# LEDs_in_top.net
KiCad netlist of a schematic drawn in EAGLE
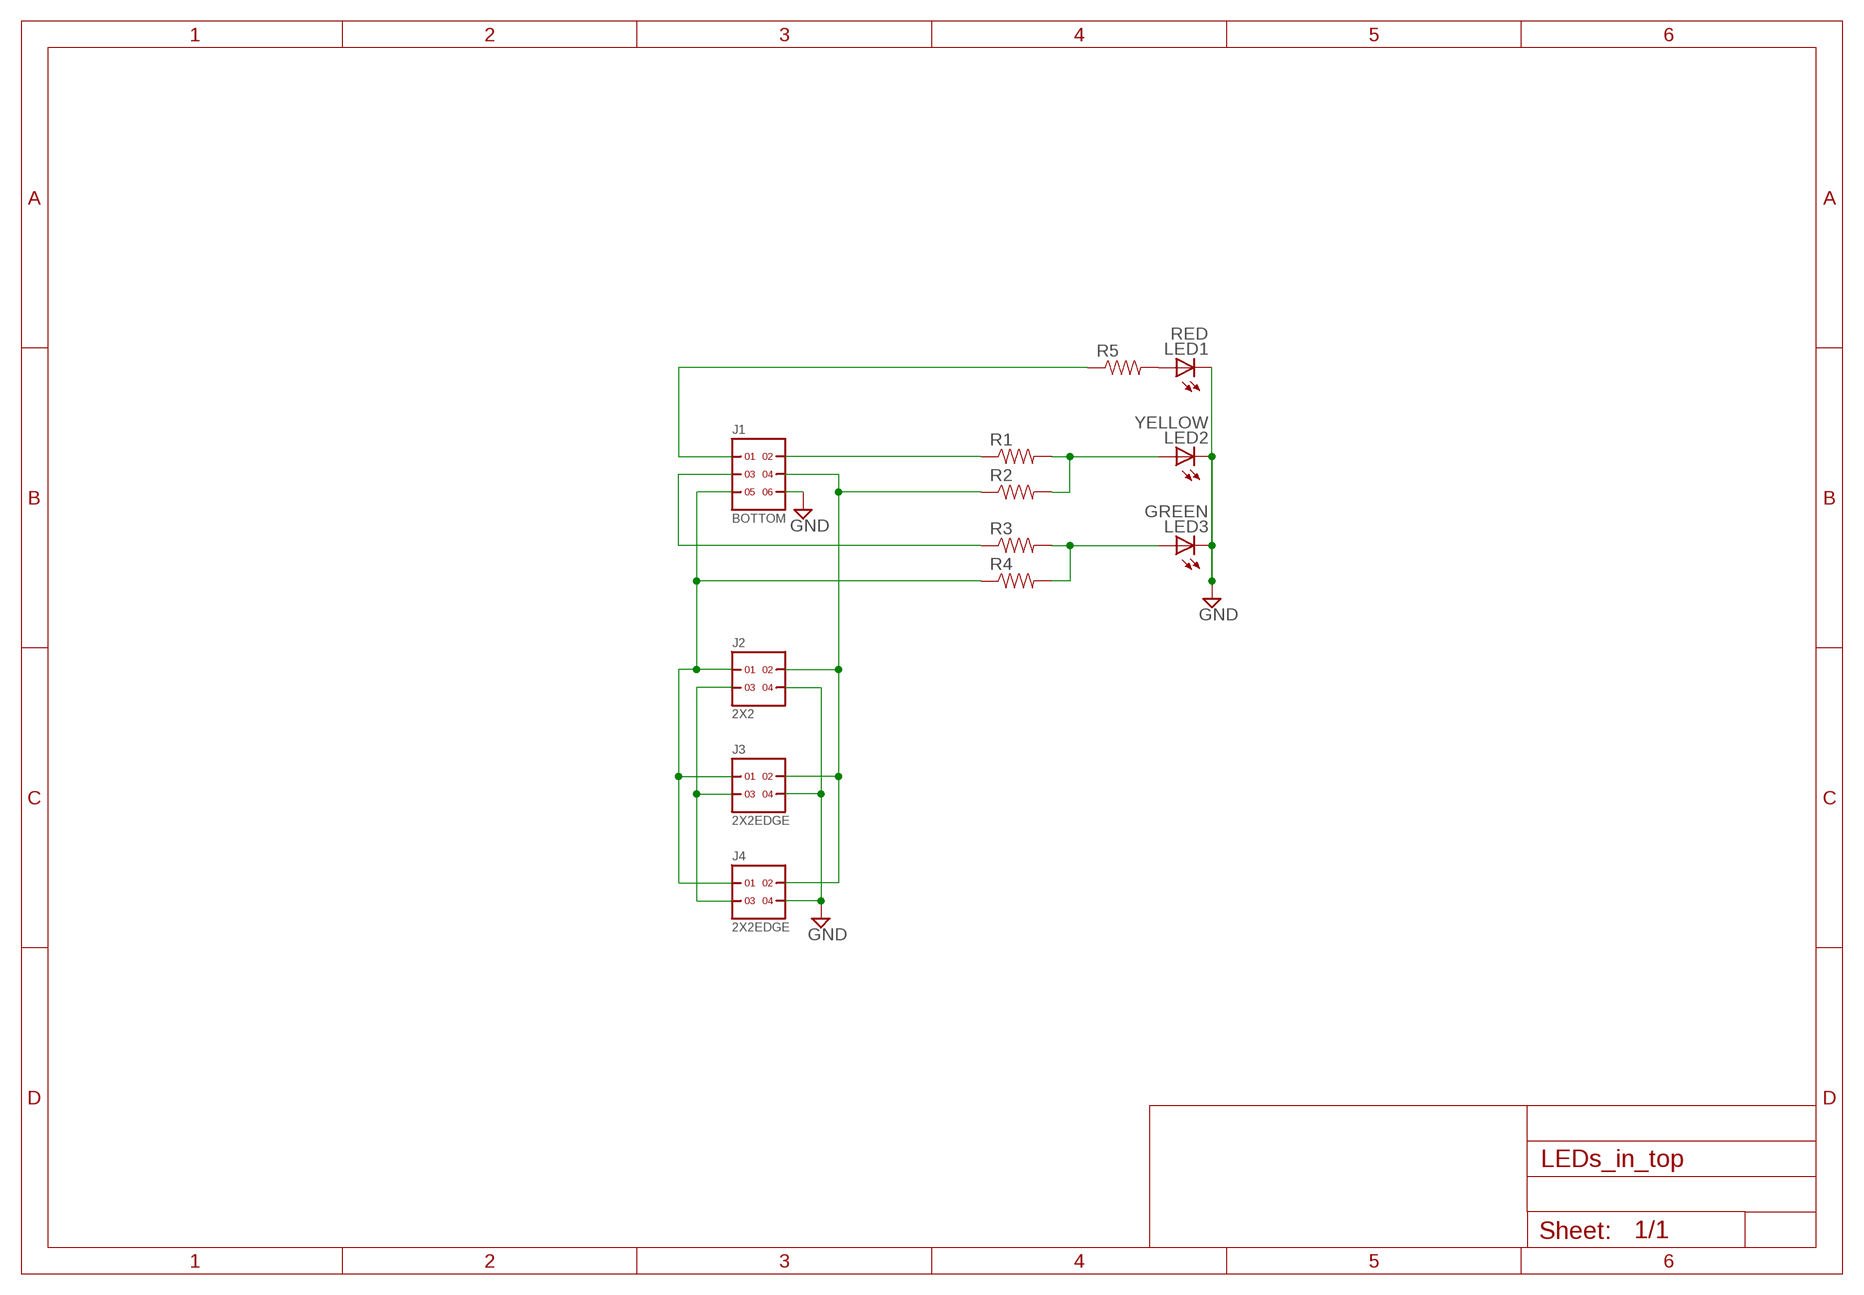
[diagram p0: schematic, sheet 1]

(export (version "E")
  (design (tool "Eeschema 10.0.6"))
  (components
    (comp (ref "J1")
      (value "BOTTOM")
      (footprint "eagle-import:2X3-2MM-EDGE")
      (libsource (lib "eagle-import") (part "2X3EDGE"))
    )
    (comp (ref "J2")
      (value "2X2")
      (footprint "eagle-import:2X2_MMT.103.01.X.DH")
      (libsource (lib "eagle-import") (part "2X2"))
    )
    (comp (ref "J3")
      (value "2X2EDGE")
      (footprint "eagle-import:2X2-2MM-EDGE")
      (libsource (lib "eagle-import") (part "2X2EDGE"))
    )
    (comp (ref "J4")
      (value "2X2EDGE")
      (footprint "eagle-import:2X2-2MM-EDGE")
      (libsource (lib "eagle-import") (part "2X2EDGE"))
    )
    (comp (ref "LED1")
      (value "RED")
      (footprint "eagle-import:CHIP-LED0805")
      (libsource (lib "eagle-import") (part "LEDCHIP-LED0805"))
    )
    (comp (ref "LED2")
      (value "YELLOW")
      (footprint "eagle-import:CHIP-LED0805")
      (libsource (lib "eagle-import") (part "LEDCHIP-LED0805"))
    )
    (comp (ref "LED3")
      (value "GREEN")
      (footprint "eagle-import:CHIP-LED0805")
      (libsource (lib "eagle-import") (part "LEDCHIP-LED0805"))
    )
    (comp (ref "R1")
      (value "RESISTOR0805-RES")
      (footprint "eagle-import:0805")
      (libsource (lib "eagle-import") (part "RESISTOR0805-RES"))
    )
    (comp (ref "R2")
      (value "RESISTOR0805-RES")
      (footprint "eagle-import:0805")
      (libsource (lib "eagle-import") (part "RESISTOR0805-RES"))
    )
    (comp (ref "R3")
      (value "RESISTOR0805-RES")
      (footprint "eagle-import:0805")
      (libsource (lib "eagle-import") (part "RESISTOR0805-RES"))
    )
    (comp (ref "R4")
      (value "RESISTOR0805-RES")
      (footprint "eagle-import:0805")
      (libsource (lib "eagle-import") (part "RESISTOR0805-RES"))
    )
    (comp (ref "R5")
      (value "RESISTOR0805-RES")
      (footprint "eagle-import:0805")
      (libsource (lib "eagle-import") (part "RESISTOR0805-RES"))
    )
  )
  (nets
    (net (code "1") (name "GND") (class "Default")
      (node (ref "J1") (pin "6") (pinfunction "6_6") (pintype "bidirectional"))
      (node (ref "J2") (pin "4") (pinfunction "4_4") (pintype "bidirectional"))
      (node (ref "J3") (pin "4") (pinfunction "4_4") (pintype "bidirectional"))
      (node (ref "J4") (pin "4") (pinfunction "4_4") (pintype "bidirectional"))
      (node (ref "LED1") (pin "C") (pinfunction "C_C") (pintype "passive"))
      (node (ref "LED2") (pin "C") (pinfunction "C_C") (pintype "passive"))
      (node (ref "LED3") (pin "C") (pinfunction "C_C") (pintype "passive"))
    )
    (net (code "2") (name "Net-(J1-Pad1)") (class "Default")
      (node (ref "J1") (pin "1") (pinfunction "1_1") (pintype "bidirectional"))
      (node (ref "R5") (pin "1") (pinfunction "1_1") (pintype "passive"))
    )
    (net (code "3") (name "Net-(J1-Pad2)") (class "Default")
      (node (ref "J1") (pin "2") (pinfunction "2_2") (pintype "bidirectional"))
      (node (ref "R1") (pin "1") (pinfunction "1_1") (pintype "passive"))
    )
    (net (code "4") (name "Net-(J1-Pad3)") (class "Default")
      (node (ref "J1") (pin "3") (pinfunction "3_3") (pintype "bidirectional"))
      (node (ref "R3") (pin "1") (pinfunction "1_1") (pintype "passive"))
    )
    (net (code "5") (name "Net-(J1-Pad4)") (class "Default")
      (node (ref "J1") (pin "4") (pinfunction "4_4") (pintype "bidirectional"))
      (node (ref "J2") (pin "2") (pinfunction "2_2") (pintype "bidirectional"))
      (node (ref "J3") (pin "2") (pinfunction "2_2") (pintype "bidirectional"))
      (node (ref "J4") (pin "2") (pinfunction "2_2") (pintype "bidirectional"))
      (node (ref "R2") (pin "1") (pinfunction "1_1") (pintype "passive"))
    )
    (net (code "6") (name "Net-(J1-Pad5)") (class "Default")
      (node (ref "J1") (pin "5") (pinfunction "5_5") (pintype "bidirectional"))
      (node (ref "J2") (pin "1") (pinfunction "1_1") (pintype "bidirectional"))
      (node (ref "J3") (pin "1") (pinfunction "1_1") (pintype "bidirectional"))
      (node (ref "J4") (pin "1") (pinfunction "1_1") (pintype "bidirectional"))
      (node (ref "R4") (pin "1") (pinfunction "1_1") (pintype "passive"))
    )
    (net (code "7") (name "Net-(J2-Pad3)") (class "Default")
      (node (ref "J2") (pin "3") (pinfunction "3_3") (pintype "bidirectional"))
      (node (ref "J3") (pin "3") (pinfunction "3_3") (pintype "bidirectional"))
      (node (ref "J4") (pin "3") (pinfunction "3_3") (pintype "bidirectional"))
    )
    (net (code "8") (name "Net-(LED1-PadA)") (class "Default")
      (node (ref "LED1") (pin "A") (pinfunction "A_A") (pintype "passive"))
      (node (ref "R5") (pin "2") (pinfunction "2_2") (pintype "passive"))
    )
    (net (code "9") (name "Net-(LED2-PadA)") (class "Default")
      (node (ref "LED2") (pin "A") (pinfunction "A_A") (pintype "passive"))
      (node (ref "R1") (pin "2") (pinfunction "2_2") (pintype "passive"))
      (node (ref "R2") (pin "2") (pinfunction "2_2") (pintype "passive"))
    )
    (net (code "10") (name "Net-(LED3-PadA)") (class "Default")
      (node (ref "LED3") (pin "A") (pinfunction "A_A") (pintype "passive"))
      (node (ref "R3") (pin "2") (pinfunction "2_2") (pintype "passive"))
      (node (ref "R4") (pin "2") (pinfunction "2_2") (pintype "passive"))
    )
  )
)
